# salinity.net
KiCad netlist of a schematic drawn in Altium Designer
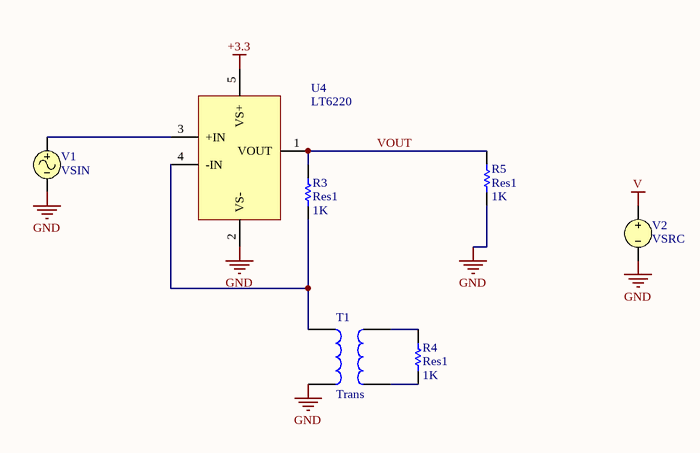
[diagram p0: salinity.SchDoc]

(export (version "E")
  (design (tool "Eeschema 10.0.6"))
  (components
    (comp (ref "R3")
      (value "Res1")
      (footprint "AXIAL-0.3")
      (description "Resistor")
      (fields (field (name "ALTIUM_VALUE") "1K") (field (name "PUBLISHER") "Altium Limited"))
      (libsource (lib "Miscellaneous Devices") (part "Res1"))
    )
    (comp (ref "R4")
      (value "Res1")
      (footprint "AXIAL-0.3")
      (description "Resistor")
      (fields (field (name "ALTIUM_VALUE") "1K") (field (name "PUBLISHER") "Altium Limited"))
      (libsource (lib "Miscellaneous Devices") (part "Res1"))
    )
    (comp (ref "R5")
      (value "Res1")
      (footprint "AXIAL-0.3")
      (description "Resistor")
      (fields (field (name "ALTIUM_VALUE") "1K") (field (name "PUBLISHER") "Altium Limited"))
      (libsource (lib "Miscellaneous Devices") (part "Res1"))
    )
    (comp (ref "T1")
      (value "Trans")
      (footprint "TRANS")
      (description "Transformer")
      (fields (field (name "PUBLISHER") "Altium Limited"))
      (libsource (lib "Miscellaneous Devices") (part "Trans"))
    )
    (comp (ref "U4") (value "LT6220") (libsource (lib "LT6220") (part "LT6220")))
    (comp (ref "V1")
      (value "VSIN")
      (description "Sinusoidal Voltage Source")
      (fields (field (name "PUBLISHER") "Altium Limited"))
      (libsource (lib "Simulation Sources") (part "VSIN"))
    )
    (comp (ref "V2")
      (value "VSRC")
      (description "Voltage Source")
      (fields (field (name "PUBLISHER") "Altium Limited"))
      (libsource (lib "Simulation Sources") (part "VSRC"))
    )
  )
  (nets
    (net (code "1") (name "+3.3") (class "Default")
      (node (ref "U4") (pin "5") (pinfunction "VS+_5") (pintype "power_in"))
    )
    (net (code "2") (name "/VOUT") (class "Default")
      (node (ref "R3") (pin "2") (pinfunction "2_2") (pintype "passive"))
      (node (ref "R5") (pin "2") (pinfunction "2_2") (pintype "passive"))
      (node (ref "U4") (pin "1") (pinfunction "VOUT_1") (pintype "passive"))
    )
    (net (code "3") (name "GND") (class "Default")
      (node (ref "R5") (pin "1") (pinfunction "1_1") (pintype "passive"))
      (node (ref "T1") (pin "2") (pinfunction "2_2") (pintype "passive"))
      (node (ref "U4") (pin "2") (pinfunction "VS-_2") (pintype "power_in"))
      (node (ref "V1") (pin "2") (pinfunction "2_2") (pintype "passive"))
      (node (ref "V2") (pin "2") (pinfunction "2_2") (pintype "passive"))
    )
    (net (code "4") (name "Net-(R4-Pad1)") (class "Default")
      (node (ref "R4") (pin "1") (pinfunction "1_1") (pintype "passive"))
      (node (ref "T1") (pin "4") (pinfunction "4_4") (pintype "passive"))
    )
    (net (code "5") (name "Net-(R4-Pad2)") (class "Default")
      (node (ref "R4") (pin "2") (pinfunction "2_2") (pintype "passive"))
      (node (ref "T1") (pin "3") (pinfunction "3_3") (pintype "passive"))
    )
    (net (code "6") (name "Net-(U4-+IN)") (class "Default")
      (node (ref "U4") (pin "3") (pinfunction "+IN_3") (pintype "passive"))
      (node (ref "V1") (pin "1") (pinfunction "1_1") (pintype "passive"))
    )
    (net (code "7") (name "Net-(U4--IN)") (class "Default")
      (node (ref "R3") (pin "1") (pinfunction "1_1") (pintype "passive"))
      (node (ref "T1") (pin "1") (pinfunction "1_1") (pintype "passive"))
      (node (ref "U4") (pin "4") (pinfunction "-IN_4") (pintype "passive"))
    )
    (net (code "8") (name "V") (class "Default")
      (node (ref "V2") (pin "1") (pinfunction "1_1") (pintype "passive"))
    )
  )
)
